# PowerSupply.net
KiCad netlist of a schematic drawn in Altium Designer
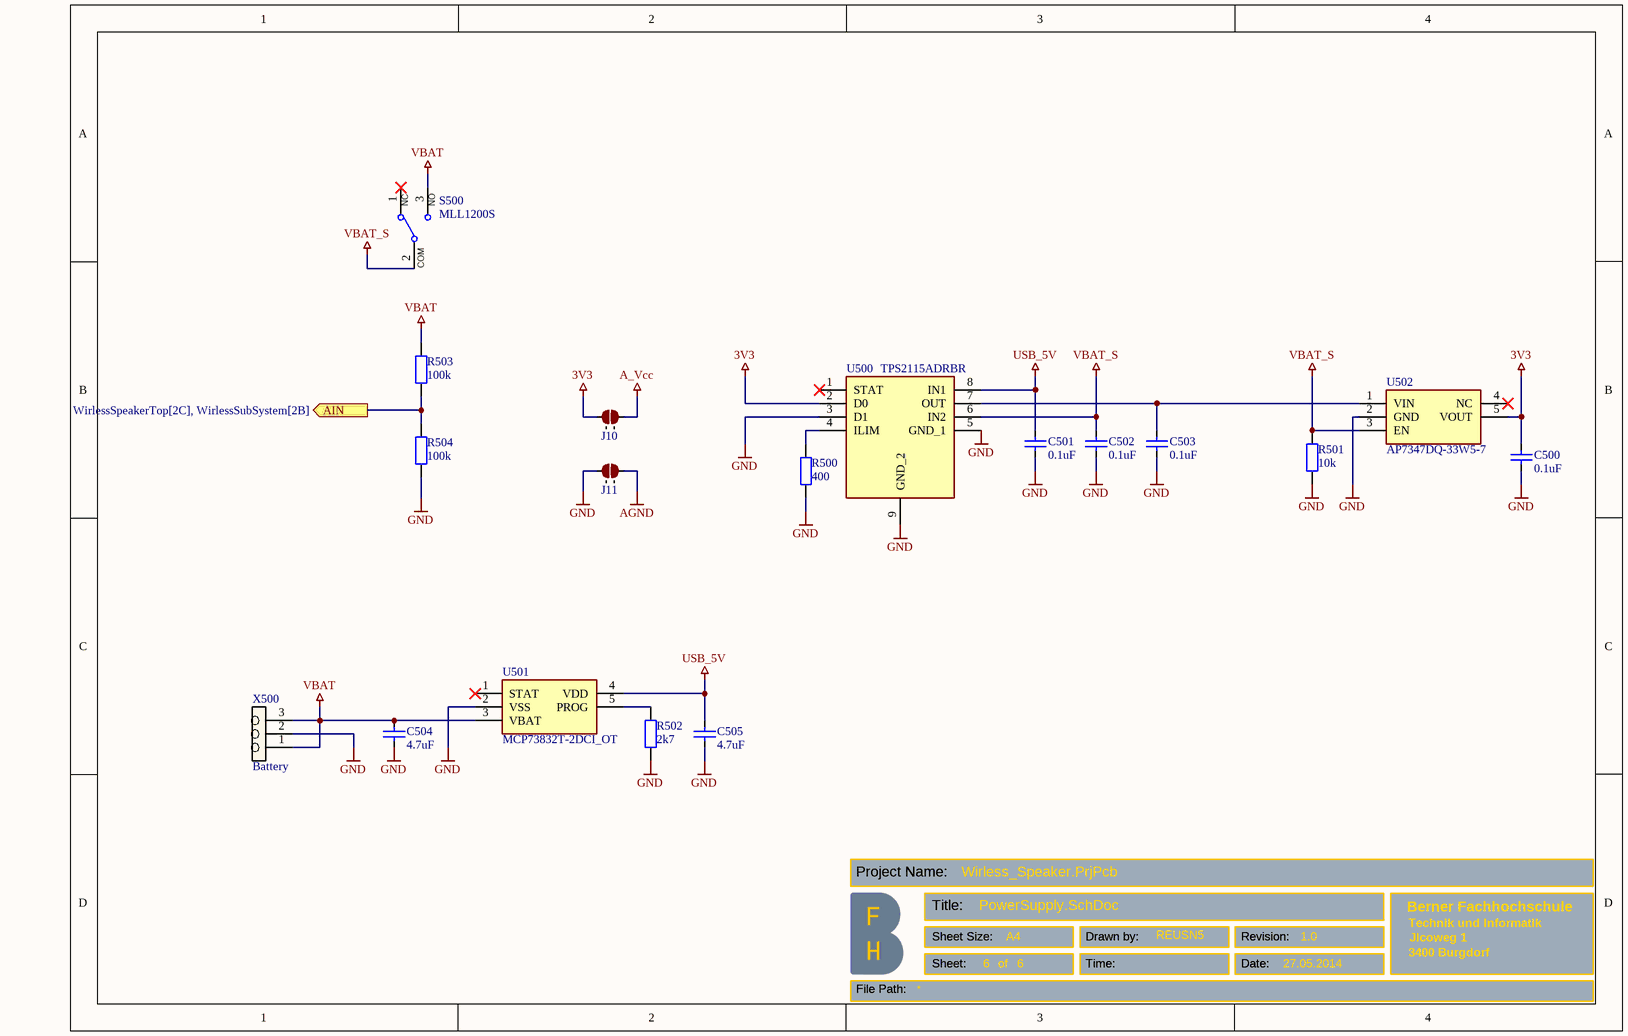
[diagram p0: PowerSupply.SchDoc]

(export (version "E")
  (design (tool "Eeschema 10.0.6"))
  (components
    (comp (ref "C500")
      (value "0.1uF")
      (footprint "C-0603")
      (description "Multilayer Ceramic Capacitors MLCC")
      (fields (field (name "MANUFACTURER") "Murata Electronics") (field (name "MFR. PART NO.") "GRM18..."))
      (libsource (lib "WirelessAudioSpeaker") (part "C-SMD-0603"))
    )
    (comp (ref "C501")
      (value "0.1uF")
      (footprint "C-0603")
      (description "Multilayer Ceramic Capacitors MLCC")
      (fields (field (name "MANUFACTURER") "Murata Electronics") (field (name "MFR. PART NO.") "GRM18..."))
      (libsource (lib "WirelessAudioSpeaker") (part "C-SMD-0603"))
    )
    (comp (ref "C502")
      (value "0.1uF")
      (footprint "C-0603")
      (description "Multilayer Ceramic Capacitors MLCC")
      (fields (field (name "MANUFACTURER") "Murata Electronics") (field (name "MFR. PART NO.") "GRM18..."))
      (libsource (lib "WirelessAudioSpeaker") (part "C-SMD-0603"))
    )
    (comp (ref "C503")
      (value "0.1uF")
      (footprint "C-0603")
      (description "Multilayer Ceramic Capacitors MLCC")
      (fields (field (name "MANUFACTURER") "Murata Electronics") (field (name "MFR. PART NO.") "GRM18..."))
      (libsource (lib "WirelessAudioSpeaker") (part "C-SMD-0603"))
    )
    (comp (ref "C504")
      (value "4.7uF")
      (footprint "C-0603")
      (description "Multilayer Ceramic Capacitors MLCC")
      (fields (field (name "MANUFACTURER") "Murata Electronics") (field (name "MFR. PART NO.") "GRM18..."))
      (libsource (lib "WirelessAudioSpeaker") (part "C-SMD-0603"))
    )
    (comp (ref "C505")
      (value "4.7uF")
      (footprint "C-0603")
      (description "Multilayer Ceramic Capacitors MLCC")
      (fields (field (name "MANUFACTURER") "Murata Electronics") (field (name "MFR. PART NO.") "GRM18..."))
      (libsource (lib "WirelessAudioSpeaker") (part "C-SMD-0603"))
    )
    (comp (ref "J10")
      (value "2 way net solder junction - Normally Open")
      (footprint "2waySolder_NO")
      (libsource (lib "NetTie") (part "2waySolderNO"))
    )
    (comp (ref "J11")
      (value "2 way net solder junction - Normally Open")
      (footprint "2waySolder_NO")
      (libsource (lib "NetTie") (part "2waySolderNO"))
    )
    (comp (ref "R500")
      (value "400")
      (footprint "R-0603")
      (description "Thin Film Resistors - SMD  0.1W  1%")
      (fields (field (name "MFR. PART NO.") "MCU08050C*") (field (name "MANUFACTURER") "Vishay / Beyschlag"))
      (libsource (lib "WirelessAudioSpeaker") (part "R-SMD-0603"))
    )
    (comp (ref "R501")
      (value "10k")
      (footprint "R-0603")
      (description "Thin Film Resistors - SMD  0.1W  1%")
      (fields (field (name "MFR. PART NO.") "MCU08050C*") (field (name "MANUFACTURER") "Vishay / Beyschlag"))
      (libsource (lib "WirelessAudioSpeaker") (part "R-SMD-0603"))
    )
    (comp (ref "R502")
      (value "2k7")
      (footprint "R-0603")
      (description "Thin Film Resistors - SMD  0.1W  1%")
      (fields (field (name "MFR. PART NO.") "MCU08050C*") (field (name "MANUFACTURER") "Vishay / Beyschlag"))
      (libsource (lib "WirelessAudioSpeaker") (part "R-SMD-0603"))
    )
    (comp (ref "R503")
      (value "100k")
      (footprint "R-0603")
      (description "Thin Film Resistors - SMD  0.1W  1%")
      (fields (field (name "MFR. PART NO.") "MCU08050C*") (field (name "MANUFACTURER") "Vishay / Beyschlag"))
      (libsource (lib "WirelessAudioSpeaker") (part "R-SMD-0603"))
    )
    (comp (ref "R504")
      (value "100k")
      (footprint "R-0603")
      (description "Thin Film Resistors - SMD  0.1W  1%")
      (fields (field (name "MFR. PART NO.") "MCU08050C*") (field (name "MANUFACTURER") "Vishay / Beyschlag"))
      (libsource (lib "WirelessAudioSpeaker") (part "R-SMD-0603"))
    )
    (comp (ref "S500")
      (value "MLL1200S")
      (footprint "S-MLL1200S")
      (description "Slide Switch SPDT RA SMT MLL1200S")
      (fields (field (name "MANUFACTURER") "TE Connectivity"))
      (libsource (lib "WirelessAudioSpeaker") (part "S-Slide-Switch"))
    )
    (comp (ref "U500")
      (value "TPS2115ADRBR")
      (footprint "SON65P300X300X100-9N-D")
      (description "Power Supply")
      (fields (field (name "MOUSER PART NUMBER") "595-TPS2115ADRBR"))
      (libsource (lib "*") (part "TPS2115ADRBR"))
    )
    (comp (ref "U501")
      (value "MCP73832T-2DCI_OT")
      (footprint "SOT-23-5")
      (description "Integrated Circuit")
      (fields
        (field (name "MANUFACTURER_PART_NUMBER") "MCP73832T-2DCI/OT")
        (field (name "MOUSER PART NUMBER") "579-MCP73832T-2DCIOT")
      )
      (libsource (lib "*") (part "MCP73832T-2DCI_OT"))
    )
    (comp (ref "U502")
      (value "AP7347DQ-33W5-7")
      (footprint "SOT95P280X145-5N")
      (description "Integrated Circuit")
      (fields (field (name "MOUSER PART NUMBER") "621-AP7347DQ-33W5-7"))
      (libsource (lib "*") (part "AP7347DQ-33W5-7"))
    )
    (comp (ref "X500")
      (value "Battery")
      (footprint "Battery")
      (description "Battery  connection pads")
      (libsource (lib "WirelessAudioSpeaker") (part "X-Battery"))
    )
  )
  (nets
    (net (code "1") (name "/AIN") (class "Default")
      (node (ref "R503") (pin "1") (pinfunction "1_1") (pintype "passive"))
      (node (ref "R504") (pin "2") (pinfunction "2_2") (pintype "passive"))
    )
    (net (code "2") (name "3V3") (class "Default")
      (node (ref "C500") (pin "2") (pinfunction "2_2") (pintype "passive"))
      (node (ref "J10") (pin "1") (pinfunction "1_1") (pintype "passive"))
      (node (ref "U500") (pin "2") (pinfunction "D0_2") (pintype "passive"))
      (node (ref "U502") (pin "5") (pinfunction "VOUT_5") (pintype "passive"))
    )
    (net (code "3") (name "AGND") (class "Default")
      (node (ref "J11") (pin "2") (pinfunction "2_2") (pintype "passive"))
    )
    (net (code "4") (name "A_Vcc") (class "Default")
      (node (ref "J10") (pin "2") (pinfunction "2_2") (pintype "passive"))
    )
    (net (code "5") (name "GND") (class "Default")
      (node (ref "C500") (pin "1") (pinfunction "1_1") (pintype "passive"))
      (node (ref "C501") (pin "1") (pinfunction "1_1") (pintype "passive"))
      (node (ref "C502") (pin "1") (pinfunction "1_1") (pintype "passive"))
      (node (ref "C503") (pin "1") (pinfunction "1_1") (pintype "passive"))
      (node (ref "C504") (pin "1") (pinfunction "1_1") (pintype "passive"))
      (node (ref "C505") (pin "1") (pinfunction "1_1") (pintype "passive"))
      (node (ref "J11") (pin "1") (pinfunction "1_1") (pintype "passive"))
      (node (ref "R500") (pin "1") (pinfunction "1_1") (pintype "passive"))
      (node (ref "R501") (pin "1") (pinfunction "1_1") (pintype "passive"))
      (node (ref "R502") (pin "1") (pinfunction "1_1") (pintype "passive"))
      (node (ref "R504") (pin "1") (pinfunction "1_1") (pintype "passive"))
      (node (ref "U500") (pin "3") (pinfunction "D1_3") (pintype "passive"))
      (node (ref "U500") (pin "5") (pinfunction "GND_1_5") (pintype "passive"))
      (node (ref "U500") (pin "9") (pinfunction "GND_2_9") (pintype "passive"))
      (node (ref "U501") (pin "2") (pinfunction "VSS_2") (pintype "power_in"))
      (node (ref "U502") (pin "2") (pinfunction "GND_2") (pintype "passive"))
      (node (ref "X500") (pin "2") (pinfunction "2_2") (pintype "passive"))
    )
    (net (code "6") (name "Net-(U500-ILIM)") (class "Default")
      (node (ref "R500") (pin "2") (pinfunction "2_2") (pintype "passive"))
      (node (ref "U500") (pin "4") (pinfunction "ILIM_4") (pintype "passive"))
    )
    (net (code "7") (name "Net-(U500-OUT)") (class "Default")
      (node (ref "C503") (pin "2") (pinfunction "2_2") (pintype "passive"))
      (node (ref "U500") (pin "7") (pinfunction "OUT_7") (pintype "passive"))
      (node (ref "U502") (pin "1") (pinfunction "VIN_1") (pintype "passive"))
    )
    (net (code "8") (name "Net-(U501-PROG)") (class "Default")
      (node (ref "R502") (pin "2") (pinfunction "2_2") (pintype "passive"))
      (node (ref "U501") (pin "5") (pinfunction "PROG_5") (pintype "passive"))
    )
    (net (code "9") (name "USB_5V") (class "Default")
      (node (ref "C501") (pin "2") (pinfunction "2_2") (pintype "passive"))
      (node (ref "C505") (pin "2") (pinfunction "2_2") (pintype "passive"))
      (node (ref "U500") (pin "8") (pinfunction "IN1_8") (pintype "passive"))
      (node (ref "U501") (pin "4") (pinfunction "VDD_4") (pintype "power_in"))
    )
    (net (code "10") (name "VBAT") (class "Default")
      (node (ref "C504") (pin "2") (pinfunction "2_2") (pintype "passive"))
      (node (ref "R503") (pin "2") (pinfunction "2_2") (pintype "passive"))
      (node (ref "S500") (pin "3") (pinfunction "NO_3") (pintype "passive"))
      (node (ref "U501") (pin "3") (pinfunction "VBAT_3") (pintype "passive"))
      (node (ref "X500") (pin "1") (pinfunction "1_1") (pintype "passive"))
      (node (ref "X500") (pin "3") (pinfunction "3_3") (pintype "passive"))
    )
    (net (code "11") (name "VBAT_S") (class "Default")
      (node (ref "C502") (pin "2") (pinfunction "2_2") (pintype "passive"))
      (node (ref "R501") (pin "2") (pinfunction "2_2") (pintype "passive"))
      (node (ref "S500") (pin "2") (pinfunction "Common_2") (pintype "passive"))
      (node (ref "U500") (pin "6") (pinfunction "IN2_6") (pintype "passive"))
      (node (ref "U502") (pin "3") (pinfunction "EN_3") (pintype "passive"))
    )
    (net (code "12") (name "unconnected-(S500-NC-Pad1)") (class "Default")
      (node (ref "S500") (pin "1") (pinfunction "NC_1") (pintype "passive+no_connect"))
    )
    (net (code "13") (name "unconnected-(U500-STAT-Pad1)") (class "Default")
      (node (ref "U500") (pin "1") (pinfunction "STAT_1") (pintype "passive+no_connect"))
    )
    (net (code "14") (name "unconnected-(U501-STAT-Pad1)") (class "Default")
      (node (ref "U501") (pin "1") (pinfunction "STAT_1") (pintype "passive+no_connect"))
    )
    (net (code "15") (name "unconnected-(U502-NC-Pad4)") (class "Default")
      (node (ref "U502") (pin "4") (pinfunction "NC_4") (pintype "passive+no_connect"))
    )
  )
)
